# pontH.net
KiCad netlist of a schematic drawn in Altium Designer
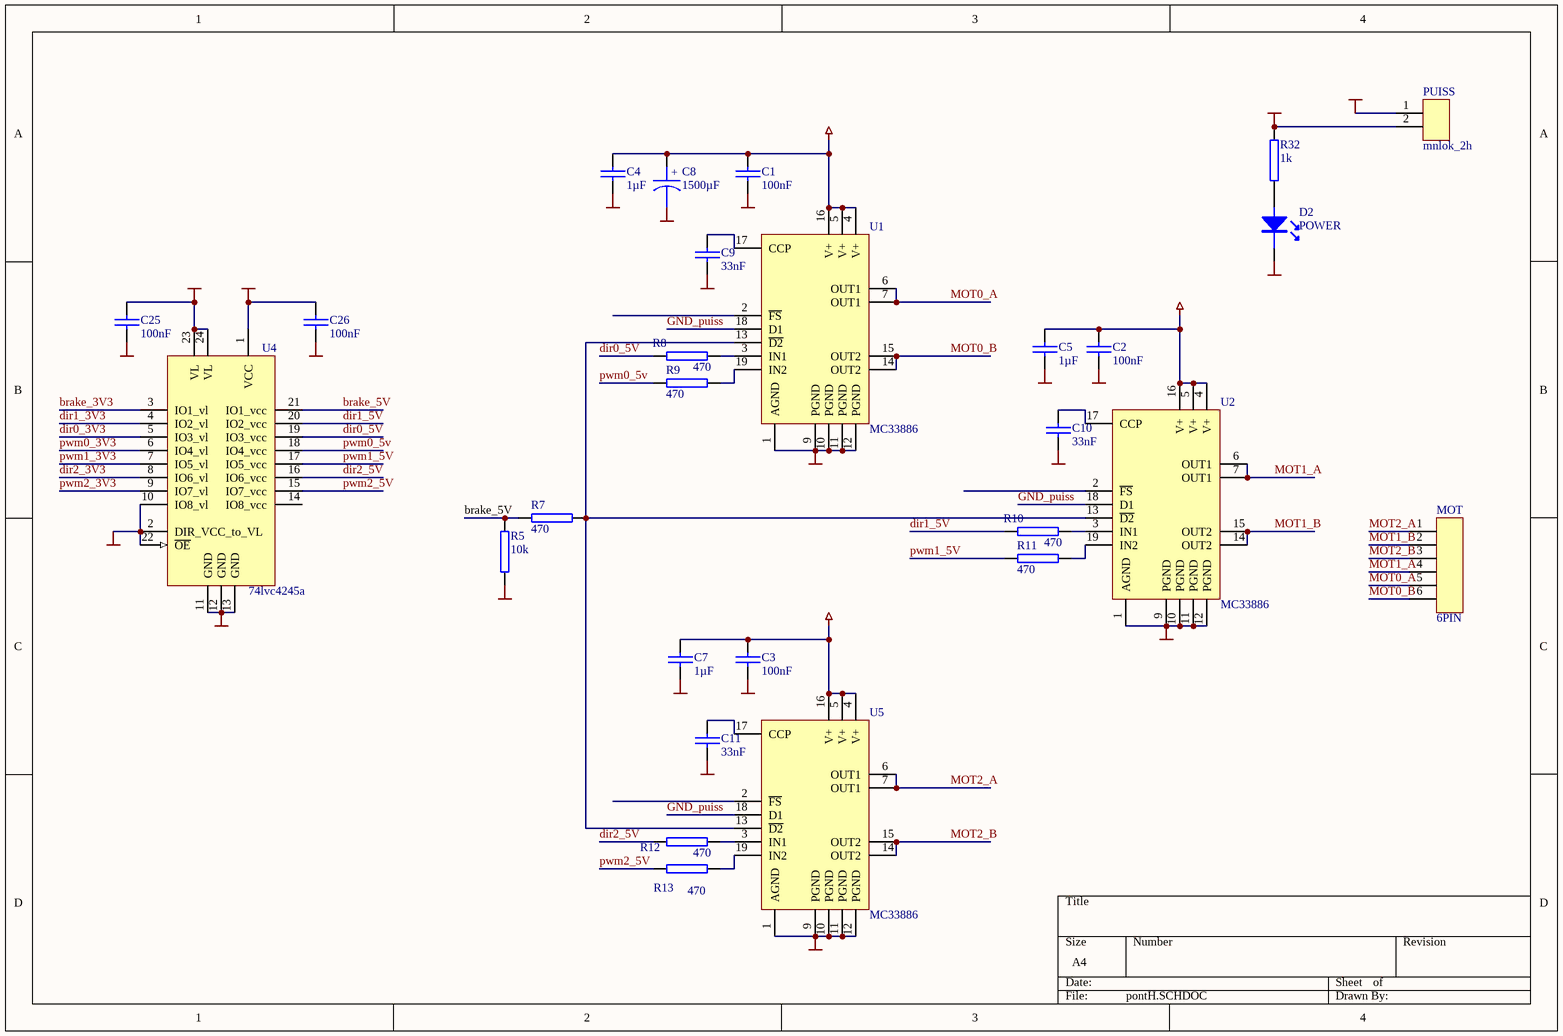
[diagram p0: pontH.SCHDOC]

(export (version "E")
  (design (tool "Eeschema 10.0.6"))
  (components
    (comp (ref "C1") (value "100nF") (footprint "TCONDO") (libsource (lib "*") (part "TCONDO")))
    (comp (ref "C2") (value "100nF") (footprint "TCONDO") (libsource (lib "*") (part "TCONDO")))
    (comp (ref "C3") (value "100nF") (footprint "TCONDO") (libsource (lib "*") (part "TCONDO")))
    (comp (ref "C4") (value "1µF") (footprint "TCONDO") (libsource (lib "*") (part "CONDO")))
    (comp (ref "C5") (value "1µF") (footprint "TCONDO") (libsource (lib "*") (part "CONDO")))
    (comp (ref "C7") (value "1µF") (footprint "TCONDO") (libsource (lib "*") (part "CONDO")))
    (comp (ref "C8")
      (value "1500µF")
      (footprint "CAPA_AXIAL_10_21")
      (libsource (lib "*") (part "CAPACITOR POL"))
    )
    (comp (ref "C9") (value "33nF") (footprint "0805") (libsource (lib "*") (part "TCONDO")))
    (comp (ref "C10") (value "33nF") (footprint "0805") (libsource (lib "*") (part "TCONDO")))
    (comp (ref "C11") (value "33nF") (footprint "0805") (libsource (lib "*") (part "TCONDO")))
    (comp (ref "C25") (value "100nF") (footprint "0805") (libsource (lib "robotter") (part "CONDO")))
    (comp (ref "C26") (value "100nF") (footprint "TCONDO") (libsource (lib "robotter") (part "CONDO")))
    (comp (ref "D2") (value "POWER") (footprint "LED_CMS") (libsource (lib "*") (part "LED_")))
    (comp (ref "MOT")
      (value "6PIN")
      (footprint "con_mat_n_lok_2*3H")
      (libsource (lib "prop2009") (part "6PIN"))
    )
    (comp (ref "PUISS")
      (value "mnlok_2h")
      (footprint "con_mat_n_lok_2h")
      (description "connecteur mat'n-lok 2 voies horizontal")
      (libsource (lib "robotter") (part "con_mat_n_lok_2h"))
    )
    (comp (ref "R5") (value "10k") (footprint "0805") (libsource (lib "*") (part "TRESIST")))
    (comp (ref "R7") (value "470") (footprint "TRES") (libsource (lib "*") (part "TRESIST")))
    (comp (ref "R8") (value "470") (footprint "0805") (libsource (lib "*") (part "TRESIST")))
    (comp (ref "R9") (value "470") (footprint "0805") (libsource (lib "*") (part "TRESIST")))
    (comp (ref "R10") (value "470") (footprint "0805") (libsource (lib "*") (part "TRESIST")))
    (comp (ref "R11") (value "470") (footprint "0805") (libsource (lib "*") (part "TRESIST")))
    (comp (ref "R12") (value "470") (footprint "0805") (libsource (lib "*") (part "TRESIST")))
    (comp (ref "R13") (value "470") (footprint "0805") (libsource (lib "*") (part "TRESIST")))
    (comp (ref "R32") (value "1k") (footprint "0805") (libsource (lib "*") (part "RES")))
    (comp (ref "U1")
      (value "MC33886")
      (footprint "HSOP20")
      (description "pont H 5A")
      (libsource (lib "*") (part "MC33886"))
    )
    (comp (ref "U2")
      (value "MC33886")
      (footprint "HSOP20")
      (description "pont H 5A")
      (libsource (lib "*") (part "MC33886"))
    )
    (comp (ref "U4")
      (value "74lvc4245a")
      (footprint "SSOP24")
      (description "octal voltage transceiver")
      (libsource (lib "prop2009") (part "74ALVC4245"))
    )
    (comp (ref "U5")
      (value "MC33886")
      (footprint "HSOP20")
      (description "pont H 5A")
      (libsource (lib "*") (part "MC33886"))
    )
  )
  (nets
    (net (code "1") (name "+BATT") (class "Default")
      (node (ref "C1") (pin "1") (pintype "passive"))
      (node (ref "C2") (pin "1") (pintype "passive"))
      (node (ref "C3") (pin "1") (pintype "passive"))
      (node (ref "C4") (pin "1") (pintype "passive"))
      (node (ref "C5") (pin "1") (pintype "passive"))
      (node (ref "C7") (pin "1") (pintype "passive"))
      (node (ref "C8") (pin "1") (pinfunction "1_1") (pintype "passive"))
      (node (ref "PUISS") (pin "2") (pinfunction "2_2") (pintype "passive"))
      (node (ref "R32") (pin "2") (pintype "passive"))
      (node (ref "U1") (pin "16") (pinfunction "V+_16") (pintype "passive"))
      (node (ref "U1") (pin "4") (pinfunction "V+_4") (pintype "passive"))
      (node (ref "U1") (pin "5") (pinfunction "V+_5") (pintype "passive"))
      (node (ref "U2") (pin "16") (pinfunction "V+_16") (pintype "passive"))
      (node (ref "U2") (pin "4") (pinfunction "V+_4") (pintype "passive"))
      (node (ref "U2") (pin "5") (pinfunction "V+_5") (pintype "passive"))
      (node (ref "U5") (pin "16") (pinfunction "V+_16") (pintype "passive"))
      (node (ref "U5") (pin "4") (pinfunction "V+_4") (pintype "passive"))
      (node (ref "U5") (pin "5") (pinfunction "V+_5") (pintype "passive"))
    )
    (net (code "2") (name "/MOT0_A") (class "Default")
      (node (ref "MOT") (pin "5") (pinfunction "5_5") (pintype "passive"))
      (node (ref "U1") (pin "6") (pinfunction "OUT1_6") (pintype "passive"))
      (node (ref "U1") (pin "7") (pinfunction "OUT1_7") (pintype "passive"))
    )
    (net (code "3") (name "/MOT0_B") (class "Default")
      (node (ref "MOT") (pin "6") (pinfunction "6_6") (pintype "passive"))
      (node (ref "U1") (pin "14") (pinfunction "OUT2_14") (pintype "passive"))
      (node (ref "U1") (pin "15") (pinfunction "OUT2_15") (pintype "passive"))
    )
    (net (code "4") (name "/MOT1_A") (class "Default")
      (node (ref "MOT") (pin "4") (pinfunction "4_4") (pintype "passive"))
      (node (ref "U2") (pin "6") (pinfunction "OUT1_6") (pintype "passive"))
      (node (ref "U2") (pin "7") (pinfunction "OUT1_7") (pintype "passive"))
    )
    (net (code "5") (name "/MOT1_B") (class "Default")
      (node (ref "MOT") (pin "2") (pinfunction "2_2") (pintype "passive"))
      (node (ref "U2") (pin "14") (pinfunction "OUT2_14") (pintype "passive"))
      (node (ref "U2") (pin "15") (pinfunction "OUT2_15") (pintype "passive"))
    )
    (net (code "6") (name "/MOT2_A") (class "Default")
      (node (ref "MOT") (pin "1") (pinfunction "1_1") (pintype "passive"))
      (node (ref "U5") (pin "6") (pinfunction "OUT1_6") (pintype "passive"))
      (node (ref "U5") (pin "7") (pinfunction "OUT1_7") (pintype "passive"))
    )
    (net (code "7") (name "/MOT2_B") (class "Default")
      (node (ref "MOT") (pin "3") (pinfunction "3_3") (pintype "passive"))
      (node (ref "U5") (pin "14") (pinfunction "OUT2_14") (pintype "passive"))
      (node (ref "U5") (pin "15") (pinfunction "OUT2_15") (pintype "passive"))
    )
    (net (code "8") (name "/brake_3V3") (class "Default")
      (node (ref "U4") (pin "3") (pinfunction "IO1_vl_3") (pintype "passive"))
    )
    (net (code "9") (name "/brake_5V") (class "Default")
      (node (ref "R5") (pin "1") (pintype "passive"))
      (node (ref "R7") (pin "2") (pintype "passive"))
      (node (ref "U4") (pin "21") (pinfunction "IO1_vcc_21") (pintype "passive"))
    )
    (net (code "10") (name "/dir0_3V3") (class "Default")
      (node (ref "U4") (pin "5") (pinfunction "IO3_vl_5") (pintype "passive"))
    )
    (net (code "11") (name "/dir0_5V") (class "Default")
      (node (ref "R8") (pin "1") (pintype "passive"))
      (node (ref "U4") (pin "19") (pinfunction "IO3_vcc_19") (pintype "passive"))
    )
    (net (code "12") (name "/dir1_3V3") (class "Default")
      (node (ref "U4") (pin "4") (pinfunction "IO2_vl_4") (pintype "passive"))
    )
    (net (code "13") (name "/dir1_5V") (class "Default")
      (node (ref "R10") (pin "1") (pintype "passive"))
      (node (ref "U4") (pin "20") (pinfunction "IO2_vcc_20") (pintype "passive"))
    )
    (net (code "14") (name "/dir2_3V3") (class "Default")
      (node (ref "U4") (pin "8") (pinfunction "IO6_vl_8") (pintype "passive"))
    )
    (net (code "15") (name "/dir2_5V") (class "Default")
      (node (ref "R12") (pin "1") (pintype "passive"))
      (node (ref "U4") (pin "16") (pinfunction "IO6_vcc_16") (pintype "passive"))
    )
    (net (code "16") (name "/pwm0_3V3") (class "Default")
      (node (ref "U4") (pin "6") (pinfunction "IO4_vl_6") (pintype "passive"))
    )
    (net (code "17") (name "/pwm0_5v") (class "Default")
      (node (ref "R9") (pin "1") (pintype "passive"))
      (node (ref "U4") (pin "18") (pinfunction "IO4_vcc_18") (pintype "passive"))
    )
    (net (code "18") (name "/pwm1_3V3") (class "Default")
      (node (ref "U4") (pin "7") (pinfunction "IO5_vl_7") (pintype "passive"))
    )
    (net (code "19") (name "/pwm1_5V") (class "Default")
      (node (ref "R11") (pin "1") (pintype "passive"))
      (node (ref "U4") (pin "17") (pinfunction "IO5_vcc_17") (pintype "passive"))
    )
    (net (code "20") (name "/pwm2_3V3") (class "Default")
      (node (ref "U4") (pin "9") (pinfunction "IO7_vl_9") (pintype "passive"))
    )
    (net (code "21") (name "/pwm2_5V") (class "Default")
      (node (ref "R13") (pin "1") (pintype "passive"))
      (node (ref "U4") (pin "15") (pinfunction "IO7_vcc_15") (pintype "passive"))
    )
    (net (code "22") (name "3V3") (class "Default")
      (node (ref "C25") (pin "1") (pintype "passive"))
      (node (ref "U4") (pin "23") (pinfunction "VL_23") (pintype "passive"))
      (node (ref "U4") (pin "24") (pinfunction "VL_24") (pintype "passive"))
    )
    (net (code "23") (name "5V") (class "Default")
      (node (ref "C26") (pin "1") (pintype "passive"))
      (node (ref "U4") (pin "1") (pinfunction "VCC_1") (pintype "passive"))
    )
    (net (code "24") (name "GND") (class "Default")
      (node (ref "C25") (pin "2") (pintype "passive"))
      (node (ref "C26") (pin "2") (pintype "passive"))
      (node (ref "R5") (pin "2") (pintype "passive"))
      (node (ref "U4") (pin "10") (pinfunction "IO8_vl_10") (pintype "passive"))
      (node (ref "U4") (pin "11") (pinfunction "GND_11") (pintype "passive"))
      (node (ref "U4") (pin "12") (pinfunction "GND_12") (pintype "passive"))
      (node (ref "U4") (pin "13") (pinfunction "GND_13") (pintype "passive"))
      (node (ref "U4") (pin "2") (pinfunction "DIR_VCC_to_VL_2") (pintype "passive"))
      (node (ref "U4") (pin "22") (pinfunction "~{OE}_22") (pintype "input"))
    )
    (net (code "25") (name "GND_puiss") (class "Default")
      (node (ref "C1") (pin "2") (pintype "passive"))
      (node (ref "C10") (pin "2") (pintype "passive"))
      (node (ref "C11") (pin "2") (pintype "passive"))
      (node (ref "C2") (pin "2") (pintype "passive"))
      (node (ref "C3") (pin "2") (pintype "passive"))
      (node (ref "C4") (pin "2") (pintype "passive"))
      (node (ref "C5") (pin "2") (pintype "passive"))
      (node (ref "C7") (pin "2") (pintype "passive"))
      (node (ref "C8") (pin "2") (pinfunction "2_2") (pintype "passive"))
      (node (ref "C9") (pin "2") (pintype "passive"))
      (node (ref "D2") (pin "2") (pinfunction "2_2") (pintype "passive"))
      (node (ref "PUISS") (pin "1") (pinfunction "1_1") (pintype "passive"))
      (node (ref "U1") (pin "1") (pinfunction "AGND_1") (pintype "passive"))
      (node (ref "U1") (pin "10") (pinfunction "PGND_10") (pintype "passive"))
      (node (ref "U1") (pin "11") (pinfunction "PGND_11") (pintype "passive"))
      (node (ref "U1") (pin "12") (pinfunction "PGND_12") (pintype "passive"))
      (node (ref "U1") (pin "18") (pinfunction "D1_18") (pintype "passive"))
      (node (ref "U1") (pin "9") (pinfunction "PGND_9") (pintype "passive"))
      (node (ref "U2") (pin "1") (pinfunction "AGND_1") (pintype "passive"))
      (node (ref "U2") (pin "10") (pinfunction "PGND_10") (pintype "passive"))
      (node (ref "U2") (pin "11") (pinfunction "PGND_11") (pintype "passive"))
      (node (ref "U2") (pin "12") (pinfunction "PGND_12") (pintype "passive"))
      (node (ref "U2") (pin "18") (pinfunction "D1_18") (pintype "passive"))
      (node (ref "U2") (pin "9") (pinfunction "PGND_9") (pintype "passive"))
      (node (ref "U5") (pin "1") (pinfunction "AGND_1") (pintype "passive"))
      (node (ref "U5") (pin "10") (pinfunction "PGND_10") (pintype "passive"))
      (node (ref "U5") (pin "11") (pinfunction "PGND_11") (pintype "passive"))
      (node (ref "U5") (pin "12") (pinfunction "PGND_12") (pintype "passive"))
      (node (ref "U5") (pin "18") (pinfunction "D1_18") (pintype "passive"))
      (node (ref "U5") (pin "9") (pinfunction "PGND_9") (pintype "passive"))
    )
    (net (code "26") (name "Net-(D2-Pad1)") (class "Default")
      (node (ref "D2") (pin "1") (pinfunction "1_1") (pintype "passive"))
      (node (ref "R32") (pin "1") (pintype "passive"))
    )
    (net (code "27") (name "Net-(U1-CCP)") (class "Default")
      (node (ref "C9") (pin "1") (pintype "passive"))
      (node (ref "U1") (pin "17") (pinfunction "CCP_17") (pintype "passive"))
    )
    (net (code "28") (name "Net-(U1-IN1)") (class "Default")
      (node (ref "R8") (pin "2") (pintype "passive"))
      (node (ref "U1") (pin "3") (pinfunction "IN1_3") (pintype "passive"))
    )
    (net (code "29") (name "Net-(U1-IN2)") (class "Default")
      (node (ref "R9") (pin "2") (pintype "passive"))
      (node (ref "U1") (pin "19") (pinfunction "IN2_19") (pintype "passive"))
    )
    (net (code "30") (name "Net-(U1-~{D2})") (class "Default")
      (node (ref "R7") (pin "1") (pintype "passive"))
      (node (ref "U1") (pin "13") (pinfunction "~{D2}_13") (pintype "passive"))
      (node (ref "U2") (pin "13") (pinfunction "~{D2}_13") (pintype "passive"))
      (node (ref "U5") (pin "13") (pinfunction "~{D2}_13") (pintype "passive"))
    )
    (net (code "31") (name "Net-(U2-CCP)") (class "Default")
      (node (ref "C10") (pin "1") (pintype "passive"))
      (node (ref "U2") (pin "17") (pinfunction "CCP_17") (pintype "passive"))
    )
    (net (code "32") (name "Net-(U2-IN1)") (class "Default")
      (node (ref "R10") (pin "2") (pintype "passive"))
      (node (ref "U2") (pin "3") (pinfunction "IN1_3") (pintype "passive"))
    )
    (net (code "33") (name "Net-(U2-IN2)") (class "Default")
      (node (ref "R11") (pin "2") (pintype "passive"))
      (node (ref "U2") (pin "19") (pinfunction "IN2_19") (pintype "passive"))
    )
    (net (code "34") (name "Net-(U5-CCP)") (class "Default")
      (node (ref "C11") (pin "1") (pintype "passive"))
      (node (ref "U5") (pin "17") (pinfunction "CCP_17") (pintype "passive"))
    )
    (net (code "35") (name "Net-(U5-IN1)") (class "Default")
      (node (ref "R12") (pin "2") (pintype "passive"))
      (node (ref "U5") (pin "3") (pinfunction "IN1_3") (pintype "passive"))
    )
    (net (code "36") (name "Net-(U5-IN2)") (class "Default")
      (node (ref "R13") (pin "2") (pintype "passive"))
      (node (ref "U5") (pin "19") (pinfunction "IN2_19") (pintype "passive"))
    )
    (net (code "37") (name "unconnected-(U1-~{FS}-Pad2)") (class "Default")
      (node (ref "U1") (pin "2") (pinfunction "~{FS}_2") (pintype "passive"))
    )
    (net (code "38") (name "unconnected-(U2-~{FS}-Pad2)") (class "Default")
      (node (ref "U2") (pin "2") (pinfunction "~{FS}_2") (pintype "passive"))
    )
    (net (code "39") (name "unconnected-(U4-IO8_vcc-Pad14)") (class "Default")
      (node (ref "U4") (pin "14") (pinfunction "IO8_vcc_14") (pintype "passive"))
    )
    (net (code "40") (name "unconnected-(U5-~{FS}-Pad2)") (class "Default")
      (node (ref "U5") (pin "2") (pinfunction "~{FS}_2") (pintype "passive"))
    )
  )
)
